# DC_DC_MPPT.net
KiCad netlist of a schematic drawn in Altium Designer
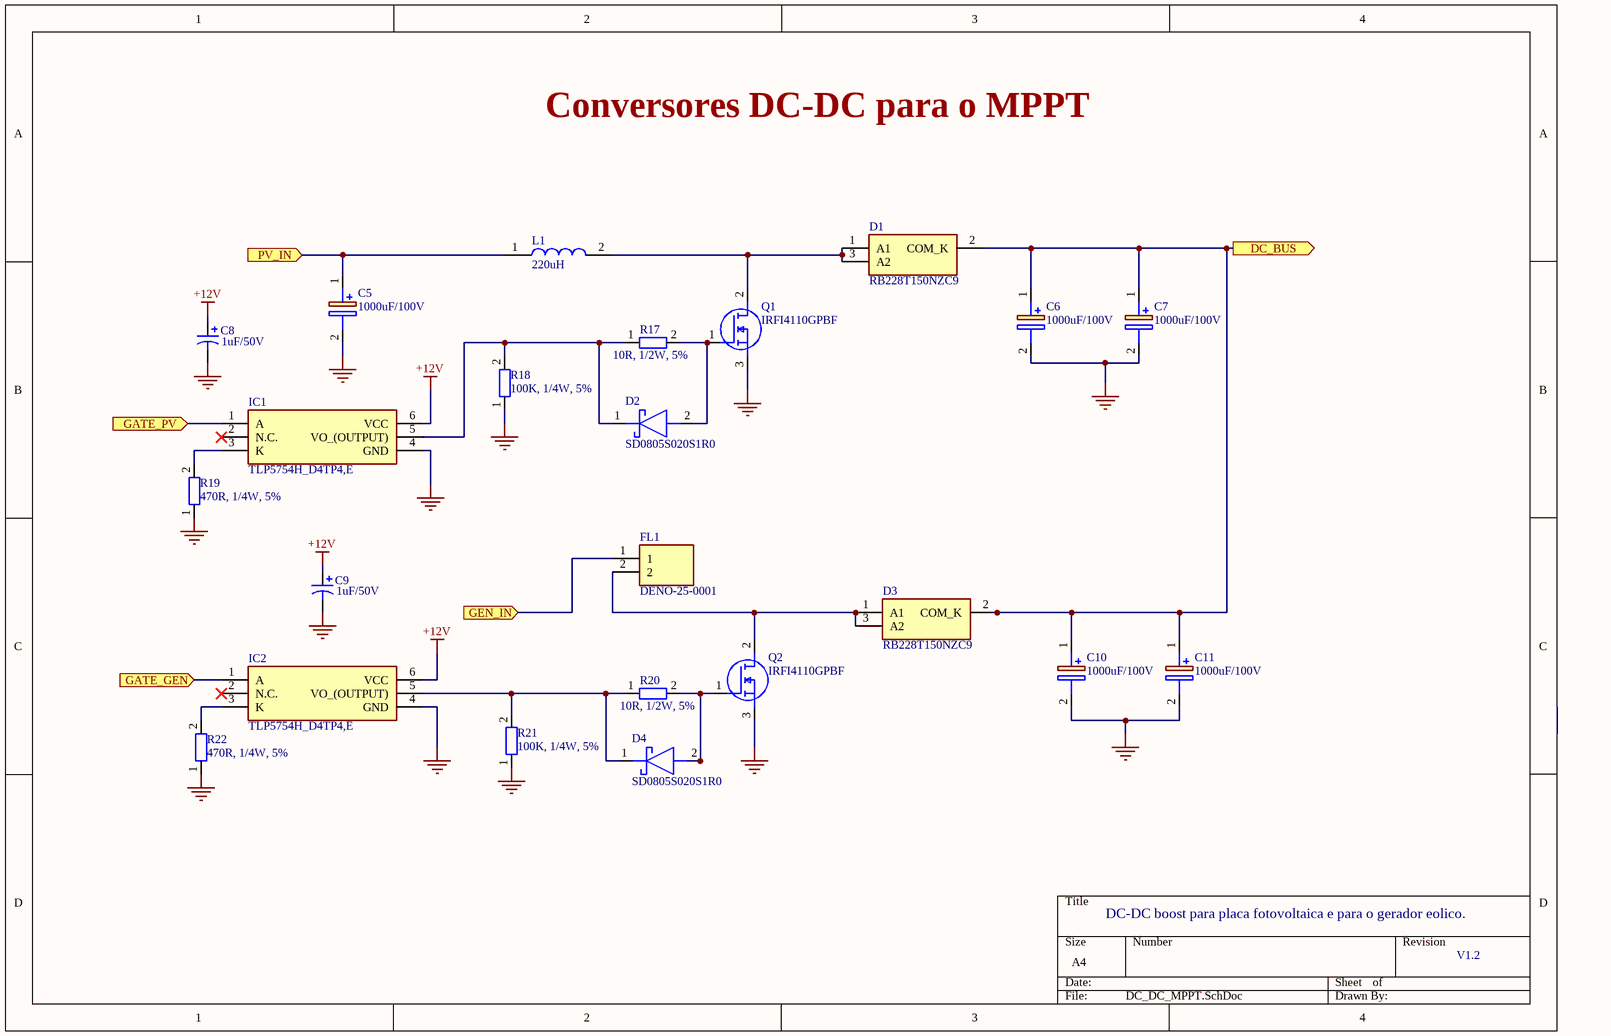
[diagram p0: DC_DC_MPPT.SchDoc]

(export (version "E")
  (design (tool "Eeschema 10.0.6"))
  (components
    (comp (ref "C5")
      (value "1000uF/100V")
      (footprint "PcbLib1:CAPPRD750W85D1800H3750")
      (description "Aluminum Electrolytic Capacitors - Leaded 1000uF 100V")
      (fields
        (field (name "MANUFACTURER_PART_NUMBER") "ECA-2AHG102")
        (field (name "MOUSER PART NUMBER") "667-ECA-2AHG102")
      )
      (libsource (lib "*") (part "ECA-2AHG102"))
    )
    (comp (ref "C6")
      (value "1000uF/100V")
      (footprint "PcbLib1:CAPPRD750W85D1800H3750")
      (description "Aluminum Electrolytic Capacitors - Leaded 1000uF 100V")
      (fields
        (field (name "MANUFACTURER_PART_NUMBER") "ECA-2AHG102")
        (field (name "MOUSER PART NUMBER") "667-ECA-2AHG102")
      )
      (libsource (lib "*") (part "ECA-2AHG102"))
    )
    (comp (ref "C7")
      (value "1000uF/100V")
      (footprint "PcbLib1:CAPPRD750W85D1800H3750")
      (description "Aluminum Electrolytic Capacitors - Leaded 1000uF 100V")
      (fields
        (field (name "MANUFACTURER_PART_NUMBER") "ECA-2AHG102")
        (field (name "MOUSER PART NUMBER") "667-ECA-2AHG102")
      )
      (libsource (lib "*") (part "ECA-2AHG102"))
    )
    (comp (ref "C8")
      (value "1uF/50V")
      (footprint "C1206")
      (fields
        (field (name "MANUFACTURER") "KEMET")
        (field (name "MANUFACTURER PART NUMBER") "T491A105K050AT")
        (field (name "TOLERANCE") "10%")
        (field (name "PUBLISHER") "Altium Limited")
      )
      (libsource (lib "Miscellaneous Devices") (part "Cap Pol1"))
    )
    (comp (ref "C9")
      (value "1uF/50V")
      (footprint "C1206")
      (fields
        (field (name "MANUFACTURER") "KEMET")
        (field (name "MANUFACTURER PART NUMBER") "T491A105K050AT")
        (field (name "TOLERANCE") "10%")
        (field (name "PUBLISHER") "Altium Limited")
      )
      (libsource (lib "Miscellaneous Devices") (part "Cap Pol1"))
    )
    (comp (ref "C10")
      (value "1000uF/100V")
      (footprint "PcbLib1:CAPPRD750W85D1800H3750")
      (description "Aluminum Electrolytic Capacitors - Leaded 1000uF 100V")
      (fields
        (field (name "MANUFACTURER_PART_NUMBER") "ECA-2AHG102")
        (field (name "MOUSER PART NUMBER") "667-ECA-2AHG102")
      )
      (libsource (lib "*") (part "ECA-2AHG102"))
    )
    (comp (ref "C11")
      (value "1000uF/100V")
      (footprint "PcbLib1:CAPPRD750W85D1800H3750")
      (description "Aluminum Electrolytic Capacitors - Leaded 1000uF 100V")
      (fields
        (field (name "MANUFACTURER_PART_NUMBER") "ECA-2AHG102")
        (field (name "MOUSER PART NUMBER") "667-ECA-2AHG102")
      )
      (libsource (lib "*") (part "ECA-2AHG102"))
    )
    (comp (ref "D1")
      (value "RB228T150NZC9")
      (footprint "PcbLib1:TO254P480X1010X2100-3P")
      (description "Schottky Diode")
      (fields (field (name "MANUFACTURER") "Rohm"))
      (libsource (lib "pi2") (part "RB228T150NZC9"))
    )
    (comp (ref "D2")
      (value "SD0805S020S1R0")
      (footprint "PcbLib1:DIOM1613X100N")
      (description "Schottky Diodes & Rectifiers 20volts 1A SIZE 0805")
      (fields
        (field (name "MOUSER PART NUMBER") "581-SD0805S020S1R0")
        (field (name "MANUFACTURER") "Kyocera AVX")
      )
      (libsource (lib "*") (part "SD0805S020S1R0"))
    )
    (comp (ref "D3")
      (value "RB228T150NZC9")
      (footprint "PcbLib1:TO254P480X1010X2100-3P")
      (description "Schottky Diode")
      (fields (field (name "MANUFACTURER") "Rohm"))
      (libsource (lib "pi2") (part "RB228T150NZC9"))
    )
    (comp (ref "D4")
      (value "SD0805S020S1R0")
      (footprint "PcbLib1:DIOM1613X100N")
      (description "Schottky Diodes & Rectifiers 20volts 1A SIZE 0805")
      (fields
        (field (name "MOUSER PART NUMBER") "581-SD0805S020S1R0")
        (field (name "MANUFACTURER") "Kyocera AVX")
      )
      (libsource (lib "*") (part "SD0805S020S1R0"))
    )
    (comp (ref "FL1")
      (value "DENO-25-0001")
      (footprint "PcbLib1:DENO250001")
      (description "Fixed Inductors DENO Grnd wire choke 16A")
      (fields (field (name "MOUSER PART NUMBER") "693-DENO-25-0001") (field (name "MANUFACTURER") "Schurter"))
      (libsource (lib "*") (part "DENO-25-0001"))
    )
    (comp (ref "IC1")
      (value "TLP5754H_D4TP4,E")
      (footprint "PcbLib1:SOIC127P1105X230-6N")
      (description "Integrated Circuit")
      (fields
        (field (name "MANUFACTURER_PART_NUMBER") "TLP5754H(D4TP4,E")
        (field (name "MOUSER PART NUMBER") "757-TLP5754HD4TP4E")
      )
      (libsource (lib "*") (part "TLP5754H_D4TP4,E"))
    )
    (comp (ref "IC2")
      (value "TLP5754H_D4TP4,E")
      (footprint "PcbLib1:SOIC127P1105X230-6N")
      (description "Integrated Circuit")
      (fields
        (field (name "MANUFACTURER_PART_NUMBER") "TLP5754H(D4TP4,E")
        (field (name "MOUSER PART NUMBER") "757-TLP5754HD4TP4E")
      )
      (libsource (lib "*") (part "TLP5754H_D4TP4,E"))
    )
    (comp (ref "L1")
      (value "220uH")
      (footprint "PcbLib1:1140221KRC")
      (description "BOURNS JW MILLER         1140-221K-RC             HIGH CURRENT CHOKE, 220UH 11.4A 10%")
      (fields
        (field (name "MANUFACTURER_PART_NUMBER") "1140-221K-RC")
        (field (name "MOUSER PART NUMBER") "542-1140-221K-RC")
      )
      (libsource (lib "pi2") (part "1140-221K-RC"))
    )
    (comp (ref "Q1")
      (value "IRFI4110GPBF")
      (footprint "PcbLib1:TO254P483X1018X2095-3P")
      (description "MOSFET N-CH 100V 72A TO220AB")
      (fields (field (name "MOUSER PART NUMBER") "942-IRFI4110GPBF") (field (name "MANUFACTURER") "Infineon"))
      (libsource (lib "*") (part "IRFI4110GPBF"))
    )
    (comp (ref "Q2")
      (value "IRFI4110GPBF")
      (footprint "PcbLib1:TO254P483X1018X2095-3P")
      (description "MOSFET N-CH 100V 72A TO220AB")
      (fields (field (name "MOUSER PART NUMBER") "942-IRFI4110GPBF") (field (name "MANUFACTURER") "Infineon"))
      (libsource (lib "*") (part "IRFI4110GPBF"))
    )
    (comp (ref "R17")
      (value "10R, 1/2W, 5%")
      (footprint "RESC3216X60N")
      (description "Res Thick Film 0805 10 Ohm 5% 0.5W(1/2W) +/-200ppm/C Pad SMD Automotive T/R")
      (fields
        (field (name "MANUFACTURER") "Vishay Dale")
        (field (name "MANUFACTURER PART NUMBER") "CRCW080510R0JNEAHP")
      )
      (libsource (lib "pi2") (part "RES-1206"))
    )
    (comp (ref "R18")
      (value "100K, 1/4W, 5%")
      (footprint "PcbLib1:RES-0805")
      (description "Thick Film Resistors 100K OHM 1%")
      (fields
        (field (name "MANUFACTURER_PART_NUMBER") "RC0805JR-131KL")
        (field (name "MOUSER PART NUMBER") "603-RC0805JR-131KL")
      )
      (libsource (lib "pi2") (part "Res-0805"))
    )
    (comp (ref "R19")
      (value "470R, 1/4W, 5%")
      (footprint "PcbLib1:RES-0805")
      (description "Thick Film Resistors - SMD 470 OHM 5%")
      (fields
        (field (name "MANUFACTURER_PART_NUMBER") "RC0805JR-131KL")
        (field (name "MOUSER PART NUMBER") "603-RC0805JR-131KL")
      )
      (libsource (lib "pi2") (part "Res-0805"))
    )
    (comp (ref "R20")
      (value "10R, 1/2W, 5%")
      (footprint "RESC3216X60N")
      (description "Res Thick Film 0805 10 Ohm 5% 0.5W(1/2W) +/-200ppm/C Pad SMD Automotive T/R")
      (fields
        (field (name "MANUFACTURER") "Vishay Dale")
        (field (name "MANUFACTURER PART NUMBER") "CRCW080510R0JNEAHP")
      )
      (libsource (lib "pi2") (part "RES-1206"))
    )
    (comp (ref "R21")
      (value "100K, 1/4W, 5%")
      (footprint "PcbLib1:RES-0805")
      (description "Thick Film Resistors 100K OHM 1%")
      (fields
        (field (name "MANUFACTURER_PART_NUMBER") "RC0805JR-131KL")
        (field (name "MOUSER PART NUMBER") "603-RC0805JR-131KL")
      )
      (libsource (lib "pi2") (part "Res-0805"))
    )
    (comp (ref "R22")
      (value "470R, 1/4W, 5%")
      (footprint "PcbLib1:RES-0805")
      (description "Thick Film Resistors - SMD 470 OHM 5%")
      (fields
        (field (name "MANUFACTURER_PART_NUMBER") "RC0805JR-131KL")
        (field (name "MOUSER PART NUMBER") "603-RC0805JR-131KL")
      )
      (libsource (lib "pi2") (part "Res-0805"))
    )
  )
  (nets
    (net (code "1") (name "+12V") (class "Default")
      (node (ref "C8") (pin "1") (pinfunction "1_1") (pintype "passive"))
      (node (ref "C9") (pin "1") (pinfunction "1_1") (pintype "passive"))
      (node (ref "IC1") (pin "6") (pinfunction "VCC_6") (pintype "passive"))
      (node (ref "IC2") (pin "6") (pinfunction "VCC_6") (pintype "passive"))
    )
    (net (code "2") (name "/DC_BUS") (class "Default")
      (node (ref "C10") (pin "1") (pinfunction "+_1") (pintype "passive"))
      (node (ref "C11") (pin "1") (pinfunction "+_1") (pintype "passive"))
      (node (ref "C6") (pin "1") (pinfunction "+_1") (pintype "passive"))
      (node (ref "C7") (pin "1") (pinfunction "+_1") (pintype "passive"))
      (node (ref "D1") (pin "2") (pinfunction "COM_K_2") (pintype "passive"))
      (node (ref "D3") (pin "2") (pinfunction "COM_K_2") (pintype "passive"))
    )
    (net (code "3") (name "/GATE_GEN") (class "Default")
      (node (ref "IC2") (pin "1") (pinfunction "A_1") (pintype "passive"))
    )
    (net (code "4") (name "/GATE_PV") (class "Default")
      (node (ref "IC1") (pin "1") (pinfunction "A_1") (pintype "passive"))
    )
    (net (code "5") (name "/GEN_IN") (class "Default")
      (node (ref "FL1") (pin "1") (pinfunction "1_1") (pintype "passive"))
    )
    (net (code "6") (name "/PV_IN") (class "Default")
      (node (ref "C5") (pin "1") (pinfunction "+_1") (pintype "passive"))
      (node (ref "L1") (pin "1") (pinfunction "1_1") (pintype "passive"))
    )
    (net (code "7") (name "GND") (class "Default")
      (node (ref "C10") (pin "2") (pinfunction "-_2") (pintype "passive"))
      (node (ref "C11") (pin "2") (pinfunction "-_2") (pintype "passive"))
      (node (ref "C5") (pin "2") (pinfunction "-_2") (pintype "passive"))
      (node (ref "C6") (pin "2") (pinfunction "-_2") (pintype "passive"))
      (node (ref "C7") (pin "2") (pinfunction "-_2") (pintype "passive"))
      (node (ref "C8") (pin "2") (pinfunction "2_2") (pintype "passive"))
      (node (ref "C9") (pin "2") (pinfunction "2_2") (pintype "passive"))
      (node (ref "IC1") (pin "4") (pinfunction "GND_4") (pintype "passive"))
      (node (ref "IC2") (pin "4") (pinfunction "GND_4") (pintype "passive"))
      (node (ref "Q1") (pin "3") (pinfunction "S_3") (pintype "passive"))
      (node (ref "Q2") (pin "3") (pinfunction "S_3") (pintype "passive"))
      (node (ref "R18") (pin "1") (pinfunction "1_1") (pintype "passive"))
      (node (ref "R19") (pin "1") (pinfunction "1_1") (pintype "passive"))
      (node (ref "R21") (pin "1") (pinfunction "1_1") (pintype "passive"))
      (node (ref "R22") (pin "1") (pinfunction "1_1") (pintype "passive"))
    )
    (net (code "8") (name "Net-(D1-A1)") (class "Default")
      (node (ref "D1") (pin "1") (pinfunction "A1_1") (pintype "passive"))
      (node (ref "D1") (pin "3") (pinfunction "A2_3") (pintype "passive"))
      (node (ref "L1") (pin "2") (pinfunction "2_2") (pintype "passive"))
      (node (ref "Q1") (pin "2") (pinfunction "D_2") (pintype "passive"))
    )
    (net (code "9") (name "Net-(D2-A)") (class "Default")
      (node (ref "D2") (pin "2") (pinfunction "A_2") (pintype "passive"))
      (node (ref "Q1") (pin "1") (pinfunction "G_1") (pintype "passive"))
      (node (ref "R17") (pin "2") (pinfunction "2_2") (pintype "passive"))
    )
    (net (code "10") (name "Net-(D2-K)") (class "Default")
      (node (ref "D2") (pin "1") (pinfunction "K_1") (pintype "passive"))
      (node (ref "IC1") (pin "5") (pinfunction "VO_(OUTPUT)_5") (pintype "passive"))
      (node (ref "R17") (pin "1") (pinfunction "1_1") (pintype "passive"))
      (node (ref "R18") (pin "2") (pinfunction "2_2") (pintype "passive"))
    )
    (net (code "11") (name "Net-(D3-A1)") (class "Default")
      (node (ref "D3") (pin "1") (pinfunction "A1_1") (pintype "passive"))
      (node (ref "D3") (pin "3") (pinfunction "A2_3") (pintype "passive"))
      (node (ref "FL1") (pin "2") (pinfunction "2_2") (pintype "passive"))
      (node (ref "Q2") (pin "2") (pinfunction "D_2") (pintype "passive"))
    )
    (net (code "12") (name "Net-(D4-A)") (class "Default")
      (node (ref "D4") (pin "2") (pinfunction "A_2") (pintype "passive"))
      (node (ref "Q2") (pin "1") (pinfunction "G_1") (pintype "passive"))
      (node (ref "R20") (pin "2") (pinfunction "2_2") (pintype "passive"))
    )
    (net (code "13") (name "Net-(D4-K)") (class "Default")
      (node (ref "D4") (pin "1") (pinfunction "K_1") (pintype "passive"))
      (node (ref "IC2") (pin "5") (pinfunction "VO_(OUTPUT)_5") (pintype "passive"))
      (node (ref "R20") (pin "1") (pinfunction "1_1") (pintype "passive"))
      (node (ref "R21") (pin "2") (pinfunction "2_2") (pintype "passive"))
    )
    (net (code "14") (name "Net-(IC1-K)") (class "Default")
      (node (ref "IC1") (pin "3") (pinfunction "K_3") (pintype "passive"))
      (node (ref "R19") (pin "2") (pinfunction "2_2") (pintype "passive"))
    )
    (net (code "15") (name "Net-(IC2-K)") (class "Default")
      (node (ref "IC2") (pin "3") (pinfunction "K_3") (pintype "passive"))
      (node (ref "R22") (pin "2") (pinfunction "2_2") (pintype "passive"))
    )
    (net (code "16") (name "unconnected-(IC1-N.C.-Pad2)") (class "Default")
      (node (ref "IC1") (pin "2") (pinfunction "N.C._2") (pintype "passive+no_connect"))
    )
    (net (code "17") (name "unconnected-(IC2-N.C.-Pad2)") (class "Default")
      (node (ref "IC2") (pin "2") (pinfunction "N.C._2") (pintype "passive+no_connect"))
    )
  )
)
